# ARDUINO_RADYO_VE_AMFI.net
KiCad netlist of a schematic drawn in EAGLE
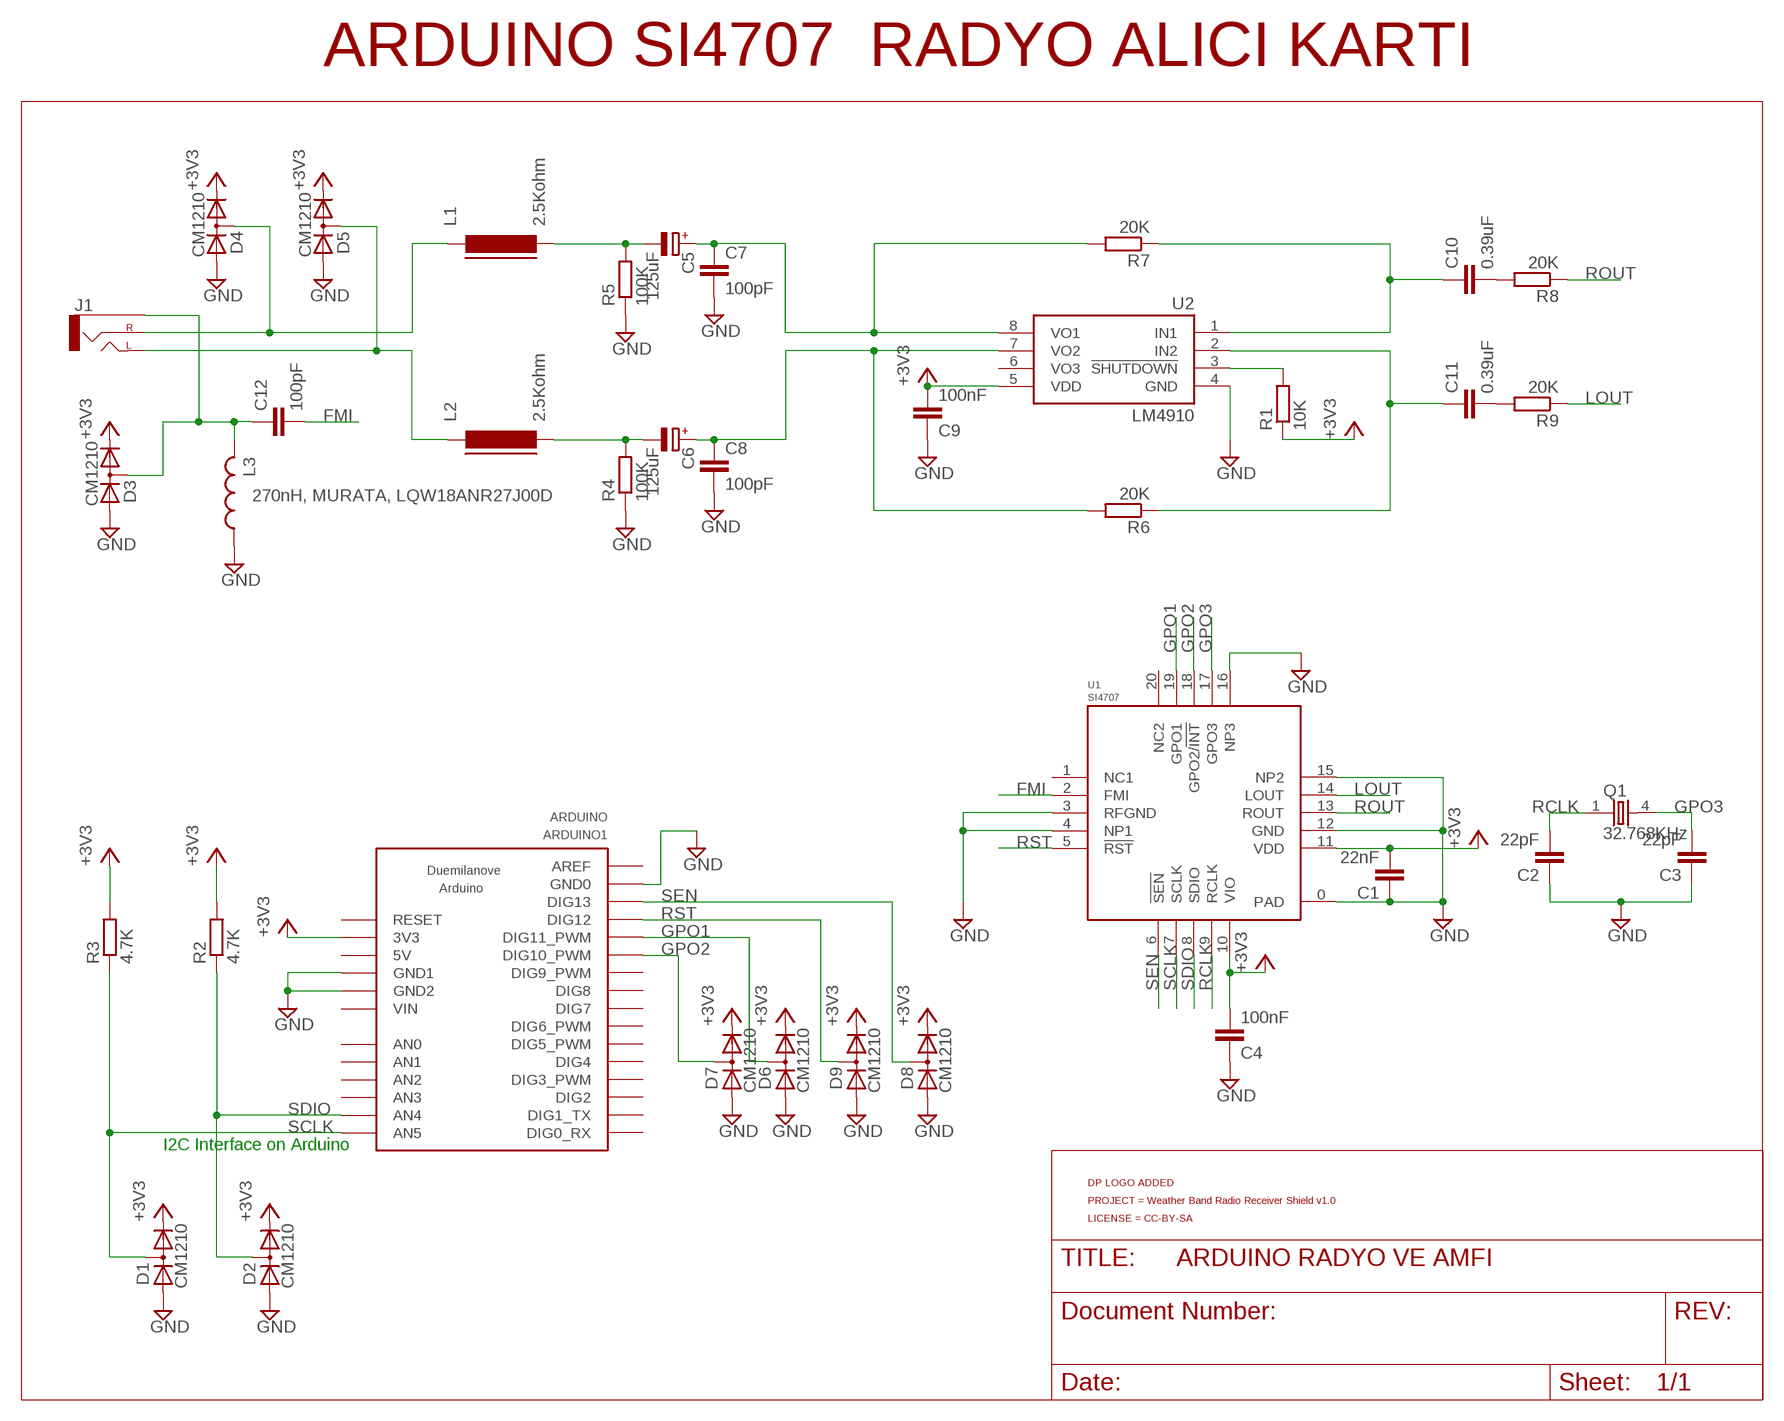
[diagram p0: schematic, sheet 1]

(export (version "E")
  (design (tool "Eeschema 10.0.6"))
  (components
    (comp (ref "ARDUINO1")
      (value "ARDUINO")
      (footprint "eagle-import:ARDUINO")
      (libsource (lib "eagle-import") (part "ARDUINO"))
    )
    (comp (ref "C1")
      (value "22nF")
      (footprint "eagle-import:C603")
      (libsource (lib "eagle-import") (part "CAPC603"))
    )
    (comp (ref "C2")
      (value "22pF")
      (footprint "eagle-import:C603")
      (libsource (lib "eagle-import") (part "CAPC603"))
    )
    (comp (ref "C3")
      (value "22pF")
      (footprint "eagle-import:C603")
      (libsource (lib "eagle-import") (part "CAPC603"))
    )
    (comp (ref "C4")
      (value "100nF")
      (footprint "eagle-import:C603")
      (libsource (lib "eagle-import") (part "CAPC603"))
    )
    (comp (ref "C5")
      (value "125uF")
      (footprint "eagle-import:SMC_B")
      (libsource (lib "eagle-import") (part "CAP_POLSMC_B"))
    )
    (comp (ref "C6")
      (value "125uF")
      (footprint "eagle-import:SMC_B")
      (libsource (lib "eagle-import") (part "CAP_POLSMC_B"))
    )
    (comp (ref "C7")
      (value "100pF")
      (footprint "eagle-import:C603")
      (libsource (lib "eagle-import") (part "CAPC603"))
    )
    (comp (ref "C8")
      (value "100pF")
      (footprint "eagle-import:C603")
      (libsource (lib "eagle-import") (part "CAPC603"))
    )
    (comp (ref "C9")
      (value "100nF")
      (footprint "eagle-import:C603")
      (libsource (lib "eagle-import") (part "CAPC603"))
    )
    (comp (ref "C10")
      (value "0.39uF")
      (footprint "eagle-import:C603")
      (libsource (lib "eagle-import") (part "CAPC603"))
    )
    (comp (ref "C11")
      (value "0.39uF")
      (footprint "eagle-import:C603")
      (libsource (lib "eagle-import") (part "CAPC603"))
    )
    (comp (ref "C12")
      (value "100pF")
      (footprint "eagle-import:C603")
      (libsource (lib "eagle-import") (part "CAPC603"))
    )
    (comp (ref "D1")
      (value "CM1210")
      (footprint "eagle-import:SOT23")
      (libsource (lib "eagle-import") (part "CM1210"))
    )
    (comp (ref "D2")
      (value "CM1210")
      (footprint "eagle-import:SOT23")
      (libsource (lib "eagle-import") (part "CM1210"))
    )
    (comp (ref "D3")
      (value "CM1210")
      (footprint "eagle-import:SOT23")
      (libsource (lib "eagle-import") (part "CM1210"))
    )
    (comp (ref "D4")
      (value "CM1210")
      (footprint "eagle-import:SOT23")
      (libsource (lib "eagle-import") (part "CM1210"))
    )
    (comp (ref "D5")
      (value "CM1210")
      (footprint "eagle-import:SOT23")
      (libsource (lib "eagle-import") (part "CM1210"))
    )
    (comp (ref "D6")
      (value "CM1210")
      (footprint "eagle-import:SOT23")
      (libsource (lib "eagle-import") (part "CM1210"))
    )
    (comp (ref "D7")
      (value "CM1210")
      (footprint "eagle-import:SOT23")
      (libsource (lib "eagle-import") (part "CM1210"))
    )
    (comp (ref "D8")
      (value "CM1210")
      (footprint "eagle-import:SOT23")
      (libsource (lib "eagle-import") (part "CM1210"))
    )
    (comp (ref "D9")
      (value "CM1210")
      (footprint "eagle-import:SOT23")
      (libsource (lib "eagle-import") (part "CM1210"))
    )
    (comp (ref "J1")
      (value "AUDIO-JACKSMD")
      (footprint "eagle-import:STEREOJACK2.5MM_SMD")
      (libsource (lib "eagle-import") (part "AUDIO-JACKSMD"))
    )
    (comp (ref "L1")
      (value "2.5Kohm")
      (footprint "eagle-import:FB603")
      (libsource (lib "eagle-import") (part "FERRITE_BEAD603"))
    )
    (comp (ref "L2")
      (value "2.5Kohm")
      (footprint "eagle-import:FB603")
      (libsource (lib "eagle-import") (part "FERRITE_BEAD603"))
    )
    (comp (ref "L3")
      (value "270nH, MURATA, LQW18ANR27J00D")
      (footprint "eagle-import:L2012C")
      (libsource (lib "eagle-import") (part "L-USL2012C"))
    )
    (comp (ref "Q1")
      (value "32.768KHz")
      (footprint "eagle-import:86SMX")
      (fields (field (name "MF") "C-MAC  FREQUENCY PRODUCTS LTD") (field (name "MPN") "XTAL003321- 86SMX"))
      (libsource (lib "eagle-import") (part "86SMX"))
    )
    (comp (ref "R1")
      (value "10K")
      (footprint "eagle-import:R603")
      (libsource (lib "eagle-import") (part "RESISTORR603"))
    )
    (comp (ref "R2")
      (value "4.7K")
      (footprint "eagle-import:R603")
      (libsource (lib "eagle-import") (part "RESISTORR603"))
    )
    (comp (ref "R3")
      (value "4.7K")
      (footprint "eagle-import:R603")
      (libsource (lib "eagle-import") (part "RESISTORR603"))
    )
    (comp (ref "R4")
      (value "100K")
      (footprint "eagle-import:R603")
      (libsource (lib "eagle-import") (part "RESISTORR603"))
    )
    (comp (ref "R5")
      (value "100K")
      (footprint "eagle-import:R603")
      (libsource (lib "eagle-import") (part "RESISTORR603"))
    )
    (comp (ref "R6")
      (value "20K")
      (footprint "eagle-import:R603")
      (libsource (lib "eagle-import") (part "RESISTORR603"))
    )
    (comp (ref "R7")
      (value "20K")
      (footprint "eagle-import:R603")
      (libsource (lib "eagle-import") (part "RESISTORR603"))
    )
    (comp (ref "R8")
      (value "20K")
      (footprint "eagle-import:R603")
      (libsource (lib "eagle-import") (part "RESISTORR603"))
    )
    (comp (ref "R9")
      (value "20K")
      (footprint "eagle-import:R603")
      (libsource (lib "eagle-import") (part "RESISTORR603"))
    )
    (comp (ref "U$1")
      (value "DP_LOGO")
      (footprint "eagle-import:DP_LOGO")
      (fields
        (field (name "LICENSE") "CC-BY-SA")
        (field (name "PROJECT") "project")
        (field (name "PROJECT_1") "Weather Band Radio Receiver Shield v1.0")
      )
      (libsource (lib "eagle-import") (part "DP_LOGO"))
    )
    (comp (ref "U1")
      (value "SI4707")
      (footprint "eagle-import:QFN-20")
      (libsource (lib "eagle-import") (part "SI4707"))
    )
    (comp (ref "U2")
      (value "LM4910")
      (footprint "eagle-import:SO8")
      (libsource (lib "eagle-import") (part "LM4910"))
    )
  )
  (nets
    (net (code "1") (name "+3V3") (class "Default")
      (node (ref "ARDUINO1") (pin "3V3") (pinfunction "3V3_3V3") (pintype "bidirectional"))
      (node (ref "C1") (pin "2") (pinfunction "2_2") (pintype "passive"))
      (node (ref "C4") (pin "2") (pinfunction "2_2") (pintype "passive"))
      (node (ref "C9") (pin "2") (pinfunction "2_2") (pintype "passive"))
      (node (ref "D1") (pin "2") (pinfunction "C_2") (pintype "passive"))
      (node (ref "D2") (pin "2") (pinfunction "C_2") (pintype "passive"))
      (node (ref "D3") (pin "2") (pinfunction "C_2") (pintype "passive"))
      (node (ref "D4") (pin "2") (pinfunction "C_2") (pintype "passive"))
      (node (ref "D5") (pin "2") (pinfunction "C_2") (pintype "passive"))
      (node (ref "D6") (pin "2") (pinfunction "C_2") (pintype "passive"))
      (node (ref "D7") (pin "2") (pinfunction "C_2") (pintype "passive"))
      (node (ref "D8") (pin "2") (pinfunction "C_2") (pintype "passive"))
      (node (ref "D9") (pin "2") (pinfunction "C_2") (pintype "passive"))
      (node (ref "R1") (pin "1") (pinfunction "1_1") (pintype "passive"))
      (node (ref "R2") (pin "2") (pinfunction "2_2") (pintype "passive"))
      (node (ref "R3") (pin "2") (pinfunction "2_2") (pintype "passive"))
      (node (ref "U1") (pin "10") (pinfunction "VIO_10") (pintype "bidirectional"))
      (node (ref "U1") (pin "11") (pinfunction "VDD_11") (pintype "bidirectional"))
      (node (ref "U2") (pin "5") (pinfunction "VDD_5") (pintype "power_in"))
    )
    (net (code "2") (name "/FMI") (class "Default")
      (node (ref "C12") (pin "2") (pinfunction "2_2") (pintype "passive"))
      (node (ref "U1") (pin "2") (pinfunction "FMI_2") (pintype "bidirectional"))
    )
    (net (code "3") (name "/GPO1") (class "Default")
      (node (ref "ARDUINO1") (pin "D_11") (pinfunction "DIG11_PWM_D_11") (pintype "bidirectional"))
      (node (ref "D6") (pin "1") (pinfunction "AC_1") (pintype "passive"))
      (node (ref "U1") (pin "19") (pinfunction "GPO1_19") (pintype "bidirectional"))
    )
    (net (code "4") (name "/GPO2") (class "Default")
      (node (ref "ARDUINO1") (pin "D_10") (pinfunction "DIG10_PWM_D_10") (pintype "bidirectional"))
      (node (ref "D7") (pin "1") (pinfunction "AC_1") (pintype "passive"))
      (node (ref "U1") (pin "18") (pinfunction "GPO2/~{INT}_18") (pintype "bidirectional"))
    )
    (net (code "5") (name "/GPO3") (class "Default")
      (node (ref "C3") (pin "2") (pinfunction "2_2") (pintype "passive"))
      (node (ref "Q1") (pin "4") (pinfunction "2_4") (pintype "passive"))
      (node (ref "U1") (pin "17") (pinfunction "GPO3_17") (pintype "bidirectional"))
    )
    (net (code "6") (name "/LOUT") (class "Default")
      (node (ref "R9") (pin "1") (pinfunction "1_1") (pintype "passive"))
      (node (ref "U1") (pin "14") (pinfunction "LOUT_14") (pintype "bidirectional"))
    )
    (net (code "7") (name "/RCLK") (class "Default")
      (node (ref "C2") (pin "2") (pinfunction "2_2") (pintype "passive"))
      (node (ref "Q1") (pin "1") (pinfunction "1_1") (pintype "passive"))
      (node (ref "U1") (pin "9") (pinfunction "RCLK_9") (pintype "bidirectional"))
    )
    (net (code "8") (name "/ROUT") (class "Default")
      (node (ref "R8") (pin "1") (pinfunction "1_1") (pintype "passive"))
      (node (ref "U1") (pin "13") (pinfunction "ROUT_13") (pintype "bidirectional"))
    )
    (net (code "9") (name "/RST") (class "Default")
      (node (ref "ARDUINO1") (pin "D_12") (pinfunction "DIG12_D_12") (pintype "bidirectional"))
      (node (ref "D9") (pin "1") (pinfunction "AC_1") (pintype "passive"))
      (node (ref "U1") (pin "5") (pinfunction "~{RST}_5") (pintype "bidirectional"))
    )
    (net (code "10") (name "/SCLK") (class "Default")
      (node (ref "ARDUINO1") (pin "A_5") (pinfunction "AN5_A_5") (pintype "input"))
      (node (ref "D1") (pin "1") (pinfunction "AC_1") (pintype "passive"))
      (node (ref "R3") (pin "1") (pinfunction "1_1") (pintype "passive"))
      (node (ref "U1") (pin "7") (pinfunction "SCLK_7") (pintype "bidirectional"))
    )
    (net (code "11") (name "/SDIO") (class "Default")
      (node (ref "ARDUINO1") (pin "A_4") (pinfunction "AN4_A_4") (pintype "input"))
      (node (ref "D2") (pin "1") (pinfunction "AC_1") (pintype "passive"))
      (node (ref "R2") (pin "1") (pinfunction "1_1") (pintype "passive"))
      (node (ref "U1") (pin "8") (pinfunction "SDIO_8") (pintype "bidirectional"))
    )
    (net (code "12") (name "/SEN") (class "Default")
      (node (ref "ARDUINO1") (pin "D_13") (pinfunction "DIG13_D_13") (pintype "bidirectional"))
      (node (ref "D8") (pin "1") (pinfunction "AC_1") (pintype "passive"))
      (node (ref "U1") (pin "6") (pinfunction "~{SEN}_6") (pintype "bidirectional"))
    )
    (net (code "13") (name "/VIN") (class "Default")
      (node (ref "ARDUINO1") (pin "VIN") (pinfunction "VIN_VIN") (pintype "power_in"))
    )
    (net (code "14") (name "GND") (class "Default")
      (node (ref "ARDUINO1") (pin "GND0") (pinfunction "GND0_GND0") (pintype "power_in"))
      (node (ref "ARDUINO1") (pin "GND1") (pinfunction "GND1_GND1") (pintype "power_in"))
      (node (ref "ARDUINO1") (pin "GND2") (pinfunction "GND2_GND2") (pintype "power_in"))
      (node (ref "C1") (pin "1") (pinfunction "1_1") (pintype "passive"))
      (node (ref "C2") (pin "1") (pinfunction "1_1") (pintype "passive"))
      (node (ref "C3") (pin "1") (pinfunction "1_1") (pintype "passive"))
      (node (ref "C4") (pin "1") (pinfunction "1_1") (pintype "passive"))
      (node (ref "C7") (pin "2") (pinfunction "2_2") (pintype "passive"))
      (node (ref "C8") (pin "2") (pinfunction "2_2") (pintype "passive"))
      (node (ref "C9") (pin "1") (pinfunction "1_1") (pintype "passive"))
      (node (ref "D1") (pin "3") (pinfunction "A_3") (pintype "passive"))
      (node (ref "D2") (pin "3") (pinfunction "A_3") (pintype "passive"))
      (node (ref "D3") (pin "3") (pinfunction "A_3") (pintype "passive"))
      (node (ref "D4") (pin "3") (pinfunction "A_3") (pintype "passive"))
      (node (ref "D5") (pin "3") (pinfunction "A_3") (pintype "passive"))
      (node (ref "D6") (pin "3") (pinfunction "A_3") (pintype "passive"))
      (node (ref "D7") (pin "3") (pinfunction "A_3") (pintype "passive"))
      (node (ref "D8") (pin "3") (pinfunction "A_3") (pintype "passive"))
      (node (ref "D9") (pin "3") (pinfunction "A_3") (pintype "passive"))
      (node (ref "L3") (pin "1") (pinfunction "1_1") (pintype "passive"))
      (node (ref "R4") (pin "1") (pinfunction "1_1") (pintype "passive"))
      (node (ref "R5") (pin "1") (pinfunction "1_1") (pintype "passive"))
      (node (ref "U1") (pin "0") (pinfunction "PAD_0") (pintype "bidirectional"))
      (node (ref "U1") (pin "12") (pinfunction "GND_12") (pintype "bidirectional"))
      (node (ref "U1") (pin "15") (pinfunction "NP2_15") (pintype "bidirectional"))
      (node (ref "U1") (pin "16") (pinfunction "NP3_16") (pintype "bidirectional"))
      (node (ref "U1") (pin "3") (pinfunction "RFGND_3") (pintype "bidirectional"))
      (node (ref "U1") (pin "4") (pinfunction "NP1_4") (pintype "bidirectional"))
      (node (ref "U2") (pin "4") (pinfunction "GND_4") (pintype "power_in"))
    )
    (net (code "15") (name "Net-(C5-Pad-)") (class "Default")
      (node (ref "C5") (pin "-") (pinfunction "-_-") (pintype "passive"))
      (node (ref "L1") (pin "2") (pinfunction "2_2") (pintype "passive"))
      (node (ref "R5") (pin "2") (pinfunction "2_2") (pintype "passive"))
    )
    (net (code "16") (name "Net-(C6-Pad-)") (class "Default")
      (node (ref "C6") (pin "-") (pinfunction "-_-") (pintype "passive"))
      (node (ref "L2") (pin "2") (pinfunction "2_2") (pintype "passive"))
      (node (ref "R4") (pin "2") (pinfunction "2_2") (pintype "passive"))
    )
    (net (code "17") (name "Net-(C10-Pad2)") (class "Default")
      (node (ref "C10") (pin "2") (pinfunction "2_2") (pintype "passive"))
      (node (ref "R8") (pin "2") (pinfunction "2_2") (pintype "passive"))
    )
    (net (code "18") (name "Net-(C11-Pad2)") (class "Default")
      (node (ref "C11") (pin "2") (pinfunction "2_2") (pintype "passive"))
      (node (ref "R9") (pin "2") (pinfunction "2_2") (pintype "passive"))
    )
    (net (code "19") (name "Net-(D3-AC)") (class "Default")
      (node (ref "C12") (pin "1") (pinfunction "1_1") (pintype "passive"))
      (node (ref "D3") (pin "1") (pinfunction "AC_1") (pintype "passive"))
      (node (ref "J1") (pin "5") (pinfunction "SLEEVE_5") (pintype "bidirectional"))
      (node (ref "L3") (pin "2") (pinfunction "2_2") (pintype "passive"))
    )
    (net (code "20") (name "Net-(D4-AC)") (class "Default")
      (node (ref "D4") (pin "1") (pinfunction "AC_1") (pintype "passive"))
      (node (ref "J1") (pin "4") (pinfunction "RIGHT_4") (pintype "bidirectional"))
      (node (ref "L1") (pin "1") (pinfunction "1_1") (pintype "passive"))
    )
    (net (code "21") (name "Net-(D5-AC)") (class "Default")
      (node (ref "D5") (pin "1") (pinfunction "AC_1") (pintype "passive"))
      (node (ref "J1") (pin "1") (pinfunction "LEFT_1") (pintype "bidirectional"))
      (node (ref "L2") (pin "1") (pinfunction "1_1") (pintype "passive"))
    )
    (net (code "22") (name "Net-(U2-IN1)") (class "Default")
      (node (ref "C10") (pin "1") (pinfunction "1_1") (pintype "passive"))
      (node (ref "R7") (pin "1") (pinfunction "1_1") (pintype "passive"))
      (node (ref "U2") (pin "1") (pinfunction "IN1_1") (pintype "input"))
    )
    (net (code "23") (name "Net-(U2-IN2)") (class "Default")
      (node (ref "C11") (pin "1") (pinfunction "1_1") (pintype "passive"))
      (node (ref "R6") (pin "1") (pinfunction "1_1") (pintype "passive"))
      (node (ref "U2") (pin "2") (pinfunction "IN2_2") (pintype "input"))
    )
    (net (code "24") (name "Net-(U2-VO1)") (class "Default")
      (node (ref "C5") (pin "+") (pinfunction "+_+") (pintype "passive"))
      (node (ref "C7") (pin "1") (pinfunction "1_1") (pintype "passive"))
      (node (ref "R7") (pin "2") (pinfunction "2_2") (pintype "passive"))
      (node (ref "U2") (pin "8") (pinfunction "VO1_8") (pintype "output"))
    )
    (net (code "25") (name "Net-(U2-VO2)") (class "Default")
      (node (ref "C6") (pin "+") (pinfunction "+_+") (pintype "passive"))
      (node (ref "C8") (pin "1") (pinfunction "1_1") (pintype "passive"))
      (node (ref "R6") (pin "2") (pinfunction "2_2") (pintype "passive"))
      (node (ref "U2") (pin "7") (pinfunction "VO2_7") (pintype "output"))
    )
    (net (code "26") (name "Net-(U2-~{SHUTDOWN})") (class "Default")
      (node (ref "R1") (pin "2") (pinfunction "2_2") (pintype "passive"))
      (node (ref "U2") (pin "3") (pinfunction "~{SHUTDOWN}_3") (pintype "input"))
    )
    (net (code "27") (name "unconnected-(ARDUINO1-AN0-PadA_0)") (class "Default")
      (node (ref "ARDUINO1") (pin "A_0") (pinfunction "AN0_A_0") (pintype "input"))
    )
    (net (code "28") (name "unconnected-(ARDUINO1-AN1-PadA_1)") (class "Default")
      (node (ref "ARDUINO1") (pin "A_1") (pinfunction "AN1_A_1") (pintype "input"))
    )
    (net (code "29") (name "unconnected-(ARDUINO1-AN2-PadA_2)") (class "Default")
      (node (ref "ARDUINO1") (pin "A_2") (pinfunction "AN2_A_2") (pintype "input"))
    )
    (net (code "30") (name "unconnected-(ARDUINO1-AN3-PadA_3)") (class "Default")
      (node (ref "ARDUINO1") (pin "A_3") (pinfunction "AN3_A_3") (pintype "input"))
    )
    (net (code "31") (name "unconnected-(ARDUINO1-DIG0_RX-PadD_0)") (class "Default")
      (node (ref "ARDUINO1") (pin "D_0") (pinfunction "DIG0_RX_D_0") (pintype "bidirectional"))
    )
    (net (code "32") (name "unconnected-(ARDUINO1-DIG1_TX-PadD_1)") (class "Default")
      (node (ref "ARDUINO1") (pin "D_1") (pinfunction "DIG1_TX_D_1") (pintype "bidirectional"))
    )
    (net (code "33") (name "unconnected-(ARDUINO1-DIG2-PadD_2)") (class "Default")
      (node (ref "ARDUINO1") (pin "D_2") (pinfunction "DIG2_D_2") (pintype "bidirectional"))
    )
    (net (code "34") (name "unconnected-(ARDUINO1-DIG3_PWM-PadD_3)") (class "Default")
      (node (ref "ARDUINO1") (pin "D_3") (pinfunction "DIG3_PWM_D_3") (pintype "bidirectional"))
    )
    (net (code "35") (name "unconnected-(ARDUINO1-DIG4-PadD_4)") (class "Default")
      (node (ref "ARDUINO1") (pin "D_4") (pinfunction "DIG4_D_4") (pintype "bidirectional"))
    )
    (net (code "36") (name "unconnected-(ARDUINO1-DIG5_PWM-PadD_5)") (class "Default")
      (node (ref "ARDUINO1") (pin "D_5") (pinfunction "DIG5_PWM_D_5") (pintype "bidirectional"))
    )
    (net (code "37") (name "unconnected-(ARDUINO1-DIG6_PWM-PadD_6)") (class "Default")
      (node (ref "ARDUINO1") (pin "D_6") (pinfunction "DIG6_PWM_D_6") (pintype "bidirectional"))
    )
    (net (code "38") (name "unconnected-(ARDUINO1-DIG7-PadD_7)") (class "Default")
      (node (ref "ARDUINO1") (pin "D_7") (pinfunction "DIG7_D_7") (pintype "bidirectional"))
    )
    (net (code "39") (name "unconnected-(ARDUINO1-DIG8-PadD_8)") (class "Default")
      (node (ref "ARDUINO1") (pin "D_8") (pinfunction "DIG8_D_8") (pintype "bidirectional"))
    )
    (net (code "40") (name "unconnected-(ARDUINO1-DIG9_PWM-PadD_9)") (class "Default")
      (node (ref "ARDUINO1") (pin "D_9") (pinfunction "DIG9_PWM_D_9") (pintype "bidirectional"))
    )
    (net (code "41") (name "unconnected-(ARDUINO1-Pad5V)") (class "Default")
      (node (ref "ARDUINO1") (pin "5V") (pinfunction "5V_5V") (pintype "bidirectional"))
    )
    (net (code "42") (name "unconnected-(ARDUINO1-PadAREF)") (class "Default")
      (node (ref "ARDUINO1") (pin "AREF") (pinfunction "AREF_AREF") (pintype "bidirectional"))
    )
    (net (code "43") (name "unconnected-(ARDUINO1-PadRESET)") (class "Default")
      (node (ref "ARDUINO1") (pin "RESET") (pinfunction "RESET_RESET") (pintype "input"))
    )
    (net (code "44") (name "unconnected-(U1-NC1-Pad1)") (class "Default")
      (node (ref "U1") (pin "1") (pinfunction "NC1_1") (pintype "bidirectional"))
    )
    (net (code "45") (name "unconnected-(U1-NC2-Pad20)") (class "Default")
      (node (ref "U1") (pin "20") (pinfunction "NC2_20") (pintype "bidirectional"))
    )
    (net (code "46") (name "unconnected-(U2-VO3-Pad6)") (class "Default")
      (node (ref "U2") (pin "6") (pinfunction "VO3_6") (pintype "output"))
    )
  )
)
